# ESCs_2S.net
KiCad netlist of a schematic drawn in Altium Designer
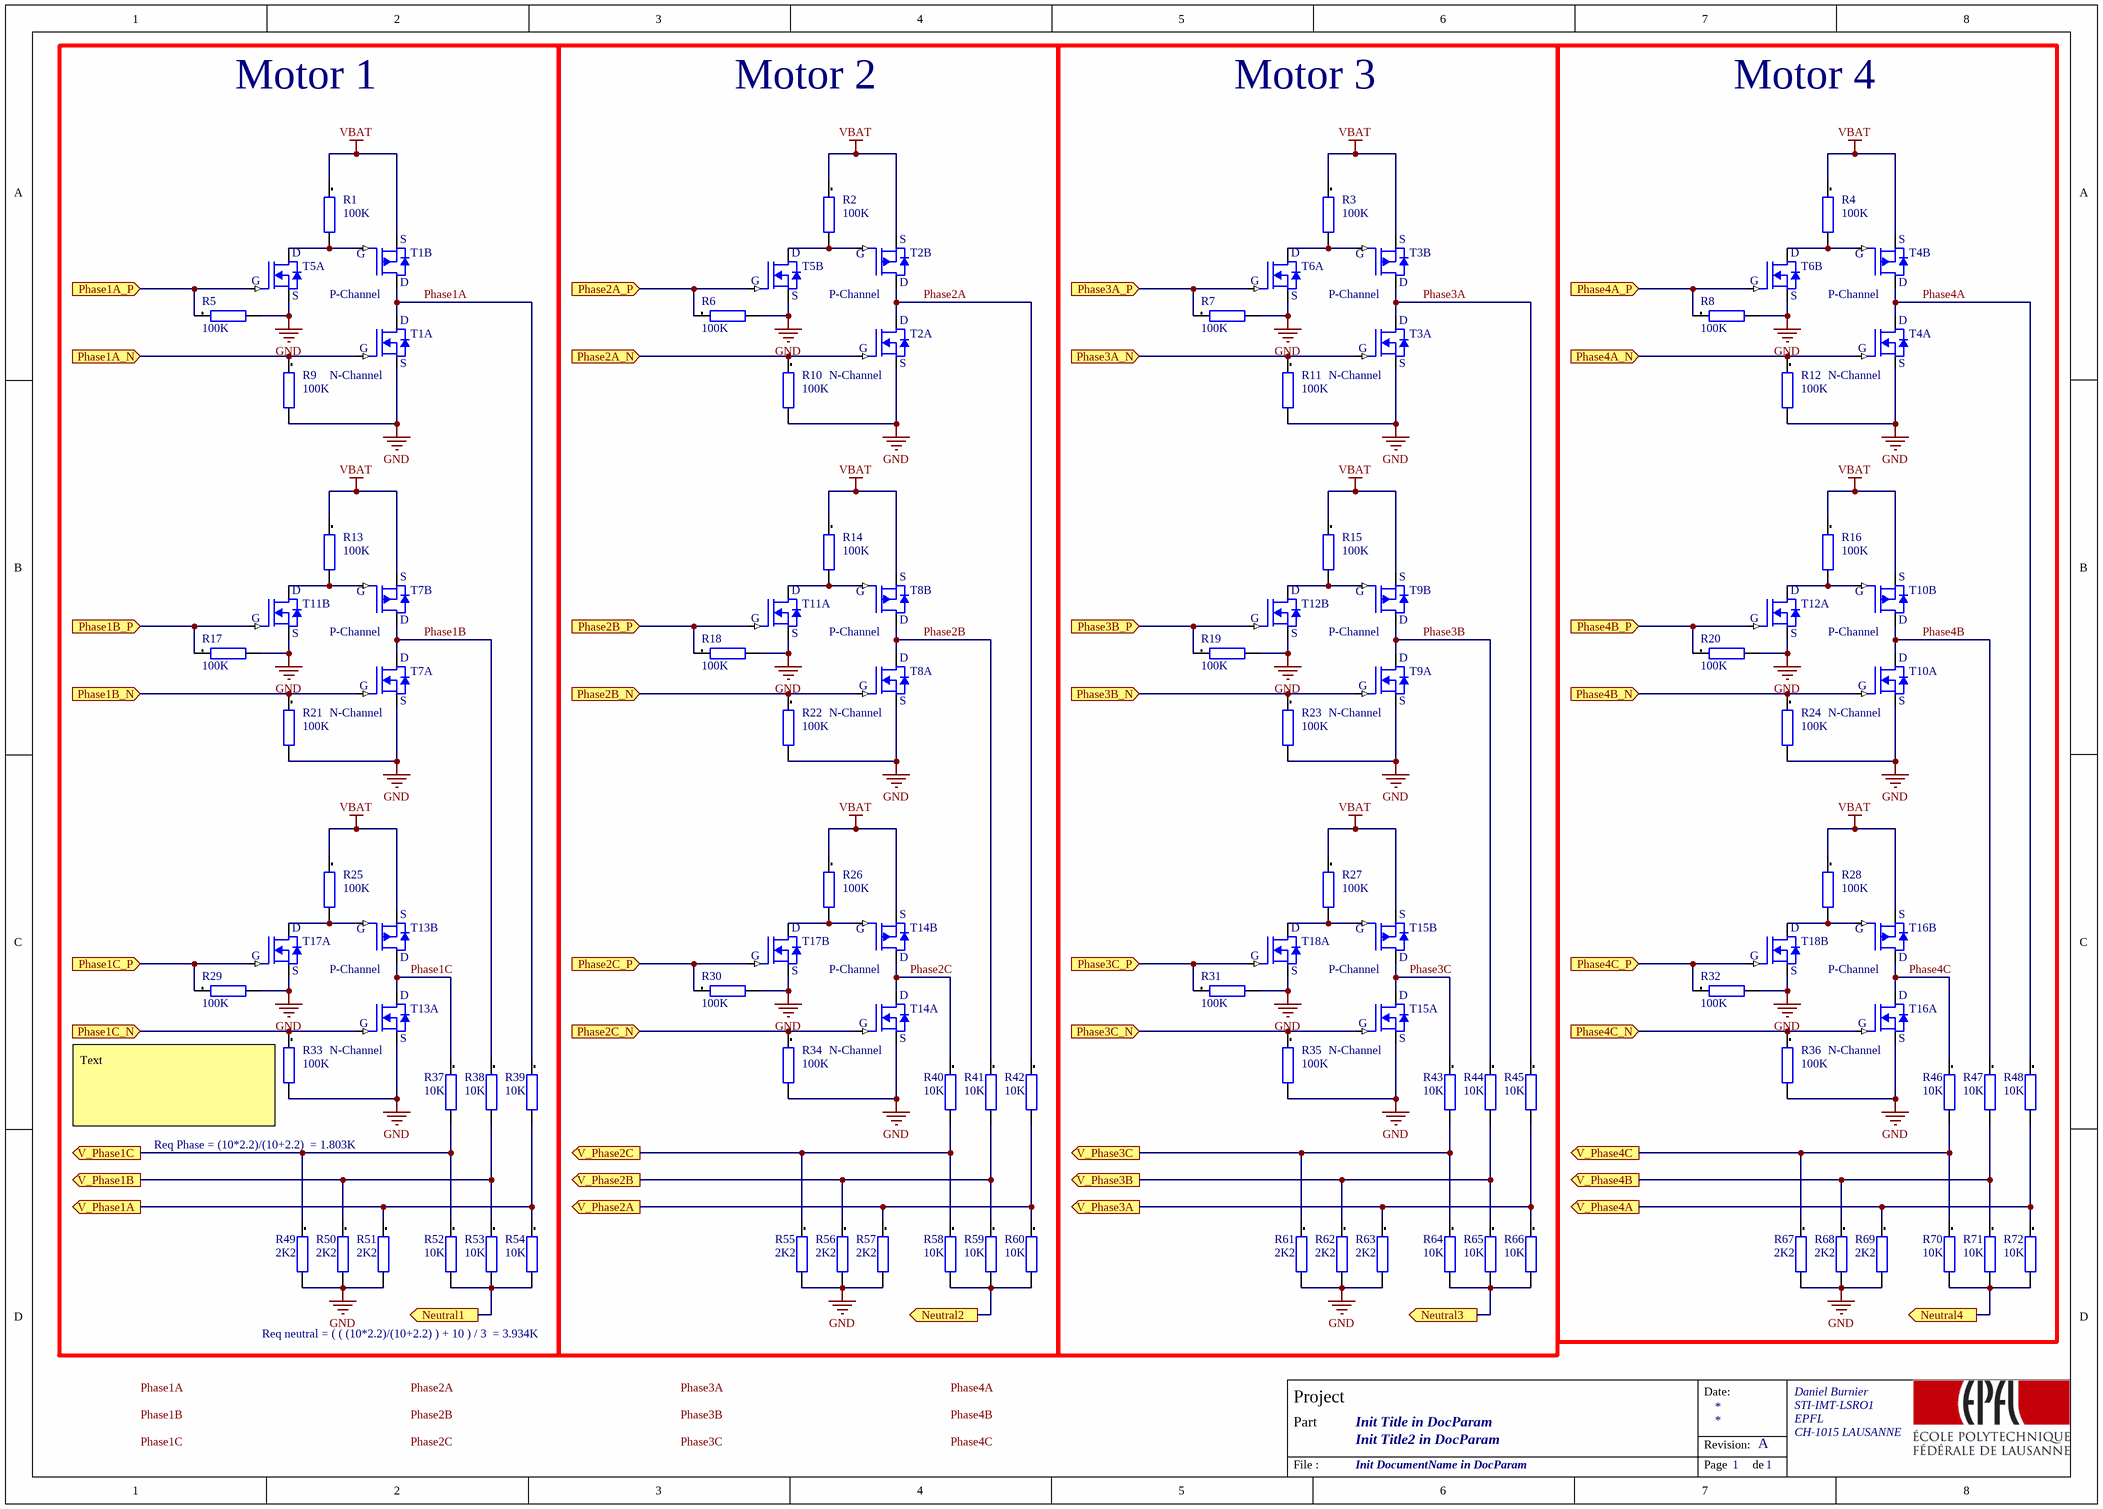
[diagram p0: ESCs_2S.SchDoc]

(export (version "E")
  (design (tool "Eeschema 10.0.6"))
  (components
    (comp (ref "R1")
      (value "100K")
      (footprint "RESC0201(0603)_L")
      (description "Resistor ToDo 0201")
      (libsource (lib "LSRO1Altium") (part "RES"))
    )
    (comp (ref "R2")
      (value "100K")
      (footprint "RESC0201(0603)_L")
      (description "Resistor ToDo 0201")
      (libsource (lib "LSRO1Altium") (part "RES"))
    )
    (comp (ref "R3")
      (value "100K")
      (footprint "RESC0201(0603)_L")
      (description "Resistor ToDo 0201")
      (libsource (lib "LSRO1Altium") (part "RES"))
    )
    (comp (ref "R4")
      (value "100K")
      (footprint "RESC0201(0603)_L")
      (description "Resistor ToDo 0201")
      (libsource (lib "LSRO1Altium") (part "RES"))
    )
    (comp (ref "R5")
      (value "100K")
      (footprint "RESC0201(0603)_L")
      (description "Resistor ToDo 0201")
      (libsource (lib "LSRO1Altium") (part "RES"))
    )
    (comp (ref "R6")
      (value "100K")
      (footprint "RESC0201(0603)_L")
      (description "Resistor ToDo 0201")
      (libsource (lib "LSRO1Altium") (part "RES"))
    )
    (comp (ref "R7")
      (value "100K")
      (footprint "RESC0201(0603)_L")
      (description "Resistor ToDo 0201")
      (libsource (lib "LSRO1Altium") (part "RES"))
    )
    (comp (ref "R8")
      (value "100K")
      (footprint "RESC0201(0603)_L")
      (description "Resistor ToDo 0201")
      (libsource (lib "LSRO1Altium") (part "RES"))
    )
    (comp (ref "R9")
      (value "100K")
      (footprint "RESC0201(0603)_L")
      (description "Resistor ToDo 0201")
      (libsource (lib "LSRO1Altium") (part "RES"))
    )
    (comp (ref "R10")
      (value "100K")
      (footprint "RESC0201(0603)_L")
      (description "Resistor ToDo 0201")
      (libsource (lib "LSRO1Altium") (part "RES"))
    )
    (comp (ref "R11")
      (value "100K")
      (footprint "RESC0201(0603)_L")
      (description "Resistor ToDo 0201")
      (libsource (lib "LSRO1Altium") (part "RES"))
    )
    (comp (ref "R12")
      (value "100K")
      (footprint "RESC0201(0603)_L")
      (description "Resistor ToDo 0201")
      (libsource (lib "LSRO1Altium") (part "RES"))
    )
    (comp (ref "R13")
      (value "100K")
      (footprint "RESC0201(0603)_L")
      (description "Resistor ToDo 0201")
      (libsource (lib "LSRO1Altium") (part "RES"))
    )
    (comp (ref "R14")
      (value "100K")
      (footprint "RESC0201(0603)_L")
      (description "Resistor ToDo 0201")
      (libsource (lib "LSRO1Altium") (part "RES"))
    )
    (comp (ref "R15")
      (value "100K")
      (footprint "RESC0201(0603)_L")
      (description "Resistor ToDo 0201")
      (libsource (lib "LSRO1Altium") (part "RES"))
    )
    (comp (ref "R16")
      (value "100K")
      (footprint "RESC0201(0603)_L")
      (description "Resistor ToDo 0201")
      (libsource (lib "LSRO1Altium") (part "RES"))
    )
    (comp (ref "R17")
      (value "100K")
      (footprint "RESC0201(0603)_L")
      (description "Resistor ToDo 0201")
      (libsource (lib "LSRO1Altium") (part "RES"))
    )
    (comp (ref "R18")
      (value "100K")
      (footprint "RESC0201(0603)_L")
      (description "Resistor ToDo 0201")
      (libsource (lib "LSRO1Altium") (part "RES"))
    )
    (comp (ref "R19")
      (value "100K")
      (footprint "RESC0201(0603)_L")
      (description "Resistor ToDo 0201")
      (libsource (lib "LSRO1Altium") (part "RES"))
    )
    (comp (ref "R20")
      (value "100K")
      (footprint "RESC0201(0603)_L")
      (description "Resistor ToDo 0201")
      (libsource (lib "LSRO1Altium") (part "RES"))
    )
    (comp (ref "R21")
      (value "100K")
      (footprint "RESC0201(0603)_L")
      (description "Resistor ToDo 0201")
      (libsource (lib "LSRO1Altium") (part "RES"))
    )
    (comp (ref "R22")
      (value "100K")
      (footprint "RESC0201(0603)_L")
      (description "Resistor ToDo 0201")
      (libsource (lib "LSRO1Altium") (part "RES"))
    )
    (comp (ref "R23")
      (value "100K")
      (footprint "RESC0201(0603)_L")
      (description "Resistor ToDo 0201")
      (libsource (lib "LSRO1Altium") (part "RES"))
    )
    (comp (ref "R24")
      (value "100K")
      (footprint "RESC0201(0603)_L")
      (description "Resistor ToDo 0201")
      (libsource (lib "LSRO1Altium") (part "RES"))
    )
    (comp (ref "R25")
      (value "100K")
      (footprint "RESC0201(0603)_L")
      (description "Resistor ToDo 0201")
      (libsource (lib "LSRO1Altium") (part "RES"))
    )
    (comp (ref "R26")
      (value "100K")
      (footprint "RESC0201(0603)_L")
      (description "Resistor ToDo 0201")
      (libsource (lib "LSRO1Altium") (part "RES"))
    )
    (comp (ref "R27")
      (value "100K")
      (footprint "RESC0201(0603)_L")
      (description "Resistor ToDo 0201")
      (libsource (lib "LSRO1Altium") (part "RES"))
    )
    (comp (ref "R28")
      (value "100K")
      (footprint "RESC0201(0603)_L")
      (description "Resistor ToDo 0201")
      (libsource (lib "LSRO1Altium") (part "RES"))
    )
    (comp (ref "R29")
      (value "100K")
      (footprint "RESC0201(0603)_L")
      (description "Resistor ToDo 0201")
      (libsource (lib "LSRO1Altium") (part "RES"))
    )
    (comp (ref "R30")
      (value "100K")
      (footprint "RESC0201(0603)_L")
      (description "Resistor ToDo 0201")
      (libsource (lib "LSRO1Altium") (part "RES"))
    )
    (comp (ref "R31")
      (value "100K")
      (footprint "RESC0201(0603)_L")
      (description "Resistor ToDo 0201")
      (libsource (lib "LSRO1Altium") (part "RES"))
    )
    (comp (ref "R32")
      (value "100K")
      (footprint "RESC0201(0603)_L")
      (description "Resistor ToDo 0201")
      (libsource (lib "LSRO1Altium") (part "RES"))
    )
    (comp (ref "R33")
      (value "100K")
      (footprint "RESC0201(0603)_L")
      (description "Resistor ToDo 0201")
      (libsource (lib "LSRO1Altium") (part "RES"))
    )
    (comp (ref "R34")
      (value "100K")
      (footprint "RESC0201(0603)_L")
      (description "Resistor ToDo 0201")
      (libsource (lib "LSRO1Altium") (part "RES"))
    )
    (comp (ref "R35")
      (value "100K")
      (footprint "RESC0201(0603)_L")
      (description "Resistor ToDo 0201")
      (libsource (lib "LSRO1Altium") (part "RES"))
    )
    (comp (ref "R36")
      (value "100K")
      (footprint "RESC0201(0603)_L")
      (description "Resistor ToDo 0201")
      (libsource (lib "LSRO1Altium") (part "RES"))
    )
    (comp (ref "R37")
      (value "10K")
      (footprint "RESC0201(0603)_L")
      (description "Resistor ToDo 0201")
      (libsource (lib "LSRO1Altium") (part "RES"))
    )
    (comp (ref "R38")
      (value "10K")
      (footprint "RESC0201(0603)_L")
      (description "Resistor ToDo 0201")
      (libsource (lib "LSRO1Altium") (part "RES"))
    )
    (comp (ref "R39")
      (value "10K")
      (footprint "RESC0201(0603)_L")
      (description "Resistor ToDo 0201")
      (libsource (lib "LSRO1Altium") (part "RES"))
    )
    (comp (ref "R40")
      (value "10K")
      (footprint "RESC0201(0603)_L")
      (description "Resistor ToDo 0201")
      (libsource (lib "LSRO1Altium") (part "RES"))
    )
    (comp (ref "R41")
      (value "10K")
      (footprint "RESC0201(0603)_L")
      (description "Resistor ToDo 0201")
      (libsource (lib "LSRO1Altium") (part "RES"))
    )
    (comp (ref "R42")
      (value "10K")
      (footprint "RESC0201(0603)_L")
      (description "Resistor ToDo 0201")
      (libsource (lib "LSRO1Altium") (part "RES"))
    )
    (comp (ref "R43")
      (value "10K")
      (footprint "RESC0201(0603)_L")
      (description "Resistor ToDo 0201")
      (libsource (lib "LSRO1Altium") (part "RES"))
    )
    (comp (ref "R44")
      (value "10K")
      (footprint "RESC0201(0603)_L")
      (description "Resistor ToDo 0201")
      (libsource (lib "LSRO1Altium") (part "RES"))
    )
    (comp (ref "R45")
      (value "10K")
      (footprint "RESC0201(0603)_L")
      (description "Resistor ToDo 0201")
      (libsource (lib "LSRO1Altium") (part "RES"))
    )
    (comp (ref "R46")
      (value "10K")
      (footprint "RESC0201(0603)_L")
      (description "Resistor ToDo 0201")
      (libsource (lib "LSRO1Altium") (part "RES"))
    )
    (comp (ref "R47")
      (value "10K")
      (footprint "RESC0201(0603)_L")
      (description "Resistor ToDo 0201")
      (libsource (lib "LSRO1Altium") (part "RES"))
    )
    (comp (ref "R48")
      (value "10K")
      (footprint "RESC0201(0603)_L")
      (description "Resistor ToDo 0201")
      (libsource (lib "LSRO1Altium") (part "RES"))
    )
    (comp (ref "R49")
      (value "2K2")
      (footprint "RESC0201(0603)_L")
      (description "Resistor ToDo 0201")
      (libsource (lib "LSRO1Altium") (part "RES"))
    )
    (comp (ref "R50")
      (value "2K2")
      (footprint "RESC0201(0603)_L")
      (description "Resistor ToDo 0201")
      (libsource (lib "LSRO1Altium") (part "RES"))
    )
    (comp (ref "R51")
      (value "2K2")
      (footprint "RESC0201(0603)_L")
      (description "Resistor ToDo 0201")
      (libsource (lib "LSRO1Altium") (part "RES"))
    )
    (comp (ref "R52")
      (value "10K")
      (footprint "RESC0201(0603)_L")
      (description "Resistor ToDo 0201")
      (libsource (lib "LSRO1Altium") (part "RES"))
    )
    (comp (ref "R53")
      (value "10K")
      (footprint "RESC0201(0603)_L")
      (description "Resistor ToDo 0201")
      (libsource (lib "LSRO1Altium") (part "RES"))
    )
    (comp (ref "R54")
      (value "10K")
      (footprint "RESC0201(0603)_L")
      (description "Resistor ToDo 0201")
      (libsource (lib "LSRO1Altium") (part "RES"))
    )
    (comp (ref "R55")
      (value "2K2")
      (footprint "RESC0201(0603)_L")
      (description "Resistor ToDo 0201")
      (libsource (lib "LSRO1Altium") (part "RES"))
    )
    (comp (ref "R56")
      (value "2K2")
      (footprint "RESC0201(0603)_L")
      (description "Resistor ToDo 0201")
      (libsource (lib "LSRO1Altium") (part "RES"))
    )
    (comp (ref "R57")
      (value "2K2")
      (footprint "RESC0201(0603)_L")
      (description "Resistor ToDo 0201")
      (libsource (lib "LSRO1Altium") (part "RES"))
    )
    (comp (ref "R58")
      (value "10K")
      (footprint "RESC0201(0603)_L")
      (description "Resistor ToDo 0201")
      (libsource (lib "LSRO1Altium") (part "RES"))
    )
    (comp (ref "R59")
      (value "10K")
      (footprint "RESC0201(0603)_L")
      (description "Resistor ToDo 0201")
      (libsource (lib "LSRO1Altium") (part "RES"))
    )
    (comp (ref "R60")
      (value "10K")
      (footprint "RESC0201(0603)_L")
      (description "Resistor ToDo 0201")
      (libsource (lib "LSRO1Altium") (part "RES"))
    )
    (comp (ref "R61")
      (value "2K2")
      (footprint "RESC0201(0603)_L")
      (description "Resistor ToDo 0201")
      (libsource (lib "LSRO1Altium") (part "RES"))
    )
    (comp (ref "R62")
      (value "2K2")
      (footprint "RESC0201(0603)_L")
      (description "Resistor ToDo 0201")
      (libsource (lib "LSRO1Altium") (part "RES"))
    )
    (comp (ref "R63")
      (value "2K2")
      (footprint "RESC0201(0603)_L")
      (description "Resistor ToDo 0201")
      (libsource (lib "LSRO1Altium") (part "RES"))
    )
    (comp (ref "R64")
      (value "10K")
      (footprint "RESC0201(0603)_L")
      (description "Resistor ToDo 0201")
      (libsource (lib "LSRO1Altium") (part "RES"))
    )
    (comp (ref "R65")
      (value "10K")
      (footprint "RESC0201(0603)_L")
      (description "Resistor ToDo 0201")
      (libsource (lib "LSRO1Altium") (part "RES"))
    )
    (comp (ref "R66")
      (value "10K")
      (footprint "RESC0201(0603)_L")
      (description "Resistor ToDo 0201")
      (libsource (lib "LSRO1Altium") (part "RES"))
    )
    (comp (ref "R67")
      (value "2K2")
      (footprint "RESC0201(0603)_L")
      (description "Resistor ToDo 0201")
      (libsource (lib "LSRO1Altium") (part "RES"))
    )
    (comp (ref "R68")
      (value "2K2")
      (footprint "RESC0201(0603)_L")
      (description "Resistor ToDo 0201")
      (libsource (lib "LSRO1Altium") (part "RES"))
    )
    (comp (ref "R69")
      (value "2K2")
      (footprint "RESC0201(0603)_L")
      (description "Resistor ToDo 0201")
      (libsource (lib "LSRO1Altium") (part "RES"))
    )
    (comp (ref "R70")
      (value "10K")
      (footprint "RESC0201(0603)_L")
      (description "Resistor ToDo 0201")
      (libsource (lib "LSRO1Altium") (part "RES"))
    )
    (comp (ref "R71")
      (value "10K")
      (footprint "RESC0201(0603)_L")
      (description "Resistor ToDo 0201")
      (libsource (lib "LSRO1Altium") (part "RES"))
    )
    (comp (ref "R72")
      (value "10K")
      (footprint "RESC0201(0603)_L")
      (description "Resistor ToDo 0201")
      (libsource (lib "LSRO1Altium") (part "RES"))
    )
    (comp (ref "T1")
      (value "ECH8668-TL-H")
      (footprint "8-SMD Flat lead")
      (description "MOSFET N/P-CH 20V 7.5A/5A ECH8")
      (fields (field (name "MANUFACTURER") "ON Semiconductor"))
      (libsource (lib "Schlib") (part "ECH8668-TL-H"))
    )
    (comp (ref "T2")
      (value "ECH8668-TL-H")
      (footprint "8-SMD Flat lead")
      (description "MOSFET N/P-CH 20V 7.5A/5A ECH8")
      (fields (field (name "MANUFACTURER") "ON Semiconductor"))
      (libsource (lib "Schlib") (part "ECH8668-TL-H"))
    )
    (comp (ref "T3")
      (value "ECH8668-TL-H")
      (footprint "8-SMD Flat lead")
      (description "MOSFET N/P-CH 20V 7.5A/5A ECH8")
      (fields (field (name "MANUFACTURER") "ON Semiconductor"))
      (libsource (lib "Schlib") (part "ECH8668-TL-H"))
    )
    (comp (ref "T4")
      (value "ECH8668-TL-H")
      (footprint "8-SMD Flat lead")
      (description "MOSFET N/P-CH 20V 7.5A/5A ECH8")
      (fields (field (name "MANUFACTURER") "ON Semiconductor"))
      (libsource (lib "Schlib") (part "ECH8668-TL-H"))
    )
    (comp (ref "T5")
      (value "PMDXB550UNEZ")
      (footprint "DFN1010B-6")
      (description "DUAL N-CHANNEL 30V")
      (fields (field (name "MANUFACTURER") "NXP Semiconductors"))
      (libsource (lib "Schlib") (part "PMDXB550UNEZ"))
    )
    (comp (ref "T6")
      (value "PMDXB550UNEZ")
      (footprint "DFN1010B-6")
      (description "DUAL N-CHANNEL 30V")
      (fields (field (name "MANUFACTURER") "NXP Semiconductors"))
      (libsource (lib "Schlib") (part "PMDXB550UNEZ"))
    )
    (comp (ref "T7")
      (value "ECH8668-TL-H")
      (footprint "8-SMD Flat lead")
      (description "MOSFET N/P-CH 20V 7.5A/5A ECH8")
      (fields (field (name "MANUFACTURER") "ON Semiconductor"))
      (libsource (lib "Schlib") (part "ECH8668-TL-H"))
    )
    (comp (ref "T8")
      (value "ECH8668-TL-H")
      (footprint "8-SMD Flat lead")
      (description "MOSFET N/P-CH 20V 7.5A/5A ECH8")
      (fields (field (name "MANUFACTURER") "ON Semiconductor"))
      (libsource (lib "Schlib") (part "ECH8668-TL-H"))
    )
    (comp (ref "T9")
      (value "ECH8668-TL-H")
      (footprint "8-SMD Flat lead")
      (description "MOSFET N/P-CH 20V 7.5A/5A ECH8")
      (fields (field (name "MANUFACTURER") "ON Semiconductor"))
      (libsource (lib "Schlib") (part "ECH8668-TL-H"))
    )
    (comp (ref "T10")
      (value "ECH8668-TL-H")
      (footprint "8-SMD Flat lead")
      (description "MOSFET N/P-CH 20V 7.5A/5A ECH8")
      (fields (field (name "MANUFACTURER") "ON Semiconductor"))
      (libsource (lib "Schlib") (part "ECH8668-TL-H"))
    )
    (comp (ref "T11")
      (value "PMDXB550UNEZ")
      (footprint "DFN1010B-6")
      (description "DUAL N-CHANNEL 30V")
      (fields (field (name "MANUFACTURER") "NXP Semiconductors"))
      (libsource (lib "Schlib") (part "PMDXB550UNEZ"))
    )
    (comp (ref "T12")
      (value "PMDXB550UNEZ")
      (footprint "DFN1010B-6")
      (description "DUAL N-CHANNEL 30V")
      (fields (field (name "MANUFACTURER") "NXP Semiconductors"))
      (libsource (lib "Schlib") (part "PMDXB550UNEZ"))
    )
    (comp (ref "T13")
      (value "ECH8668-TL-H")
      (footprint "8-SMD Flat lead")
      (description "MOSFET N/P-CH 20V 7.5A/5A ECH8")
      (fields (field (name "MANUFACTURER") "ON Semiconductor"))
      (libsource (lib "Schlib") (part "ECH8668-TL-H"))
    )
    (comp (ref "T14")
      (value "ECH8668-TL-H")
      (footprint "8-SMD Flat lead")
      (description "MOSFET N/P-CH 20V 7.5A/5A ECH8")
      (fields (field (name "MANUFACTURER") "ON Semiconductor"))
      (libsource (lib "Schlib") (part "ECH8668-TL-H"))
    )
    (comp (ref "T15")
      (value "ECH8668-TL-H")
      (footprint "8-SMD Flat lead")
      (description "MOSFET N/P-CH 20V 7.5A/5A ECH8")
      (fields (field (name "MANUFACTURER") "ON Semiconductor"))
      (libsource (lib "Schlib") (part "ECH8668-TL-H"))
    )
    (comp (ref "T16")
      (value "ECH8668-TL-H")
      (footprint "8-SMD Flat lead")
      (description "MOSFET N/P-CH 20V 7.5A/5A ECH8")
      (fields (field (name "MANUFACTURER") "ON Semiconductor"))
      (libsource (lib "Schlib") (part "ECH8668-TL-H"))
    )
    (comp (ref "T17")
      (value "PMDXB550UNEZ")
      (footprint "DFN1010B-6")
      (description "DUAL N-CHANNEL 30V")
      (fields (field (name "MANUFACTURER") "NXP Semiconductors"))
      (libsource (lib "Schlib") (part "PMDXB550UNEZ"))
    )
    (comp (ref "T18")
      (value "PMDXB550UNEZ")
      (footprint "DFN1010B-6")
      (description "DUAL N-CHANNEL 30V")
      (fields (field (name "MANUFACTURER") "NXP Semiconductors"))
      (libsource (lib "Schlib") (part "PMDXB550UNEZ"))
    )
  )
  (nets
    (net (code "1") (name "/Neutral1") (class "Default")
      (node (ref "R52") (pin "2") (pinfunction "2_2") (pintype "passive"))
      (node (ref "R53") (pin "2") (pinfunction "2_2") (pintype "passive"))
      (node (ref "R54") (pin "2") (pinfunction "2_2") (pintype "passive"))
    )
    (net (code "2") (name "/Neutral2") (class "Default")
      (node (ref "R58") (pin "2") (pinfunction "2_2") (pintype "passive"))
      (node (ref "R59") (pin "2") (pinfunction "2_2") (pintype "passive"))
      (node (ref "R60") (pin "2") (pinfunction "2_2") (pintype "passive"))
    )
    (net (code "3") (name "/Neutral3") (class "Default")
      (node (ref "R64") (pin "2") (pinfunction "2_2") (pintype "passive"))
      (node (ref "R65") (pin "2") (pinfunction "2_2") (pintype "passive"))
      (node (ref "R66") (pin "2") (pinfunction "2_2") (pintype "passive"))
    )
    (net (code "4") (name "/Neutral4") (class "Default")
      (node (ref "R70") (pin "2") (pinfunction "2_2") (pintype "passive"))
      (node (ref "R71") (pin "2") (pinfunction "2_2") (pintype "passive"))
      (node (ref "R72") (pin "2") (pinfunction "2_2") (pintype "passive"))
    )
    (net (code "5") (name "/Phase1A") (class "Default")
      (node (ref "R39") (pin "1") (pinfunction "1_1") (pintype "passive"))
      (node (ref "T1") (pin "5") (pinfunction "D_5") (pintype "passive"))
      (node (ref "T1") (pin "6") (pinfunction "D_6") (pintype "passive"))
    )
    (net (code "6") (name "/Phase1A_N") (class "Default")
      (node (ref "R9") (pin "1") (pinfunction "1_1") (pintype "passive"))
      (node (ref "T1") (pin "2") (pinfunction "G_2") (pintype "input"))
    )
    (net (code "7") (name "/Phase1A_P") (class "Default")
      (node (ref "R5") (pin "1") (pinfunction "1_1") (pintype "passive"))
      (node (ref "T5") (pin "2") (pinfunction "G_2") (pintype "input"))
    )
    (net (code "8") (name "/Phase1B") (class "Default")
      (node (ref "R38") (pin "1") (pinfunction "1_1") (pintype "passive"))
      (node (ref "T7") (pin "5") (pinfunction "D_5") (pintype "passive"))
      (node (ref "T7") (pin "6") (pinfunction "D_6") (pintype "passive"))
    )
    (net (code "9") (name "/Phase1B_N") (class "Default")
      (node (ref "R21") (pin "1") (pinfunction "1_1") (pintype "passive"))
      (node (ref "T7") (pin "2") (pinfunction "G_2") (pintype "input"))
    )
    (net (code "10") (name "/Phase1B_P") (class "Default")
      (node (ref "R17") (pin "1") (pinfunction "1_1") (pintype "passive"))
      (node (ref "T11") (pin "5") (pinfunction "G_5") (pintype "input"))
    )
    (net (code "11") (name "/Phase1C") (class "Default")
      (node (ref "R37") (pin "1") (pinfunction "1_1") (pintype "passive"))
      (node (ref "T13") (pin "5") (pinfunction "D_5") (pintype "passive"))
      (node (ref "T13") (pin "6") (pinfunction "D_6") (pintype "passive"))
    )
    (net (code "12") (name "/Phase1C_N") (class "Default")
      (node (ref "R33") (pin "1") (pinfunction "1_1") (pintype "passive"))
      (node (ref "T13") (pin "2") (pinfunction "G_2") (pintype "input"))
    )
    (net (code "13") (name "/Phase1C_P") (class "Default")
      (node (ref "R29") (pin "1") (pinfunction "1_1") (pintype "passive"))
      (node (ref "T17") (pin "2") (pinfunction "G_2") (pintype "input"))
    )
    (net (code "14") (name "/Phase2A") (class "Default")
      (node (ref "R42") (pin "1") (pinfunction "1_1") (pintype "passive"))
      (node (ref "T2") (pin "5") (pinfunction "D_5") (pintype "passive"))
      (node (ref "T2") (pin "6") (pinfunction "D_6") (pintype "passive"))
    )
    (net (code "15") (name "/Phase2A_N") (class "Default")
      (node (ref "R10") (pin "1") (pinfunction "1_1") (pintype "passive"))
      (node (ref "T2") (pin "2") (pinfunction "G_2") (pintype "input"))
    )
    (net (code "16") (name "/Phase2A_P") (class "Default")
      (node (ref "R6") (pin "1") (pinfunction "1_1") (pintype "passive"))
      (node (ref "T5") (pin "5") (pinfunction "G_5") (pintype "input"))
    )
    (net (code "17") (name "/Phase2B") (class "Default")
      (node (ref "R41") (pin "1") (pinfunction "1_1") (pintype "passive"))
      (node (ref "T8") (pin "5") (pinfunction "D_5") (pintype "passive"))
      (node (ref "T8") (pin "6") (pinfunction "D_6") (pintype "passive"))
    )
    (net (code "18") (name "/Phase2B_N") (class "Default")
      (node (ref "R22") (pin "1") (pinfunction "1_1") (pintype "passive"))
      (node (ref "T8") (pin "2") (pinfunction "G_2") (pintype "input"))
    )
    (net (code "19") (name "/Phase2B_P") (class "Default")
      (node (ref "R18") (pin "1") (pinfunction "1_1") (pintype "passive"))
      (node (ref "T11") (pin "2") (pinfunction "G_2") (pintype "input"))
    )
    (net (code "20") (name "/Phase2C") (class "Default")
      (node (ref "R40") (pin "1") (pinfunction "1_1") (pintype "passive"))
      (node (ref "T14") (pin "5") (pinfunction "D_5") (pintype "passive"))
      (node (ref "T14") (pin "6") (pinfunction "D_6") (pintype "passive"))
    )
    (net (code "21") (name "/Phase2C_N") (class "Default")
      (node (ref "R34") (pin "1") (pinfunction "1_1") (pintype "passive"))
      (node (ref "T14") (pin "2") (pinfunction "G_2") (pintype "input"))
    )
    (net (code "22") (name "/Phase2C_P") (class "Default")
      (node (ref "R30") (pin "1") (pinfunction "1_1") (pintype "passive"))
      (node (ref "T17") (pin "5") (pinfunction "G_5") (pintype "input"))
    )
    (net (code "23") (name "/Phase3A") (class "Default")
      (node (ref "R45") (pin "1") (pinfunction "1_1") (pintype "passive"))
      (node (ref "T3") (pin "5") (pinfunction "D_5") (pintype "passive"))
      (node (ref "T3") (pin "6") (pinfunction "D_6") (pintype "passive"))
    )
    (net (code "24") (name "/Phase3A_N") (class "Default")
      (node (ref "R11") (pin "1") (pinfunction "1_1") (pintype "passive"))
      (node (ref "T3") (pin "2") (pinfunction "G_2") (pintype "input"))
    )
    (net (code "25") (name "/Phase3A_P") (class "Default")
      (node (ref "R7") (pin "1") (pinfunction "1_1") (pintype "passive"))
      (node (ref "T6") (pin "2") (pinfunction "G_2") (pintype "input"))
    )
    (net (code "26") (name "/Phase3B") (class "Default")
      (node (ref "R44") (pin "1") (pinfunction "1_1") (pintype "passive"))
      (node (ref "T9") (pin "5") (pinfunction "D_5") (pintype "passive"))
      (node (ref "T9") (pin "6") (pinfunction "D_6") (pintype "passive"))
    )
    (net (code "27") (name "/Phase3B_N") (class "Default")
      (node (ref "R23") (pin "1") (pinfunction "1_1") (pintype "passive"))
      (node (ref "T9") (pin "2") (pinfunction "G_2") (pintype "input"))
    )
    (net (code "28") (name "/Phase3B_P") (class "Default")
      (node (ref "R19") (pin "1") (pinfunction "1_1") (pintype "passive"))
      (node (ref "T12") (pin "5") (pinfunction "G_5") (pintype "input"))
    )
    (net (code "29") (name "/Phase3C") (class "Default")
      (node (ref "R43") (pin "1") (pinfunction "1_1") (pintype "passive"))
      (node (ref "T15") (pin "5") (pinfunction "D_5") (pintype "passive"))
      (node (ref "T15") (pin "6") (pinfunction "D_6") (pintype "passive"))
    )
    (net (code "30") (name "/Phase3C_N") (class "Default")
      (node (ref "R35") (pin "1") (pinfunction "1_1") (pintype "passive"))
      (node (ref "T15") (pin "2") (pinfunction "G_2") (pintype "input"))
    )
    (net (code "31") (name "/Phase3C_P") (class "Default")
      (node (ref "R31") (pin "1") (pinfunction "1_1") (pintype "passive"))
      (node (ref "T18") (pin "2") (pinfunction "G_2") (pintype "input"))
    )
    (net (code "32") (name "/Phase4A") (class "Default")
      (node (ref "R48") (pin "1") (pinfunction "1_1") (pintype "passive"))
      (node (ref "T4") (pin "5") (pinfunction "D_5") (pintype "passive"))
      (node (ref "T4") (pin "6") (pinfunction "D_6") (pintype "passive"))
    )
    (net (code "33") (name "/Phase4A_N") (class "Default")
      (node (ref "R12") (pin "1") (pinfunction "1_1") (pintype "passive"))
      (node (ref "T4") (pin "2") (pinfunction "G_2") (pintype "input"))
    )
    (net (code "34") (name "/Phase4A_P") (class "Default")
      (node (ref "R8") (pin "1") (pinfunction "1_1") (pintype "passive"))
      (node (ref "T6") (pin "5") (pinfunction "G_5") (pintype "input"))
    )
    (net (code "35") (name "/Phase4B") (class "Default")
      (node (ref "R47") (pin "1") (pinfunction "1_1") (pintype "passive"))
      (node (ref "T10") (pin "5") (pinfunction "D_5") (pintype "passive"))
      (node (ref "T10") (pin "6") (pinfunction "D_6") (pintype "passive"))
    )
    (net (code "36") (name "/Phase4B_N") (class "Default")
      (node (ref "R24") (pin "1") (pinfunction "1_1") (pintype "passive"))
      (node (ref "T10") (pin "2") (pinfunction "G_2") (pintype "input"))
    )
    (net (code "37") (name "/Phase4B_P") (class "Default")
      (node (ref "R20") (pin "1") (pinfunction "1_1") (pintype "passive"))
      (node (ref "T12") (pin "2") (pinfunction "G_2") (pintype "input"))
    )
    (net (code "38") (name "/Phase4C") (class "Default")
      (node (ref "R46") (pin "1") (pinfunction "1_1") (pintype "passive"))
      (node (ref "T16") (pin "5") (pinfunction "D_5") (pintype "passive"))
      (node (ref "T16") (pin "6") (pinfunction "D_6") (pintype "passive"))
    )
    (net (code "39") (name "/Phase4C_N") (class "Default")
      (node (ref "R36") (pin "1") (pinfunction "1_1") (pintype "passive"))
      (node (ref "T16") (pin "2") (pinfunction "G_2") (pintype "input"))
    )
    (net (code "40") (name "/Phase4C_P") (class "Default")
      (node (ref "R32") (pin "1") (pinfunction "1_1") (pintype "passive"))
      (node (ref "T18") (pin "5") (pinfunction "G_5") (pintype "input"))
    )
    (net (code "41") (name "/V_Phase1A") (class "Default")
      (node (ref "R39") (pin "2") (pinfunction "2_2") (pintype "passive"))
      (node (ref "R51") (pin "1") (pinfunction "1_1") (pintype "passive"))
      (node (ref "R54") (pin "1") (pinfunction "1_1") (pintype "passive"))
    )
    (net (code "42") (name "/V_Phase1B") (class "Default")
      (node (ref "R38") (pin "2") (pinfunction "2_2") (pintype "passive"))
      (node (ref "R50") (pin "1") (pinfunction "1_1") (pintype "passive"))
      (node (ref "R53") (pin "1") (pinfunction "1_1") (pintype "passive"))
    )
    (net (code "43") (name "/V_Phase1C") (class "Default")
      (node (ref "R37") (pin "2") (pinfunction "2_2") (pintype "passive"))
      (node (ref "R49") (pin "1") (pinfunction "1_1") (pintype "passive"))
      (node (ref "R52") (pin "1") (pinfunction "1_1") (pintype "passive"))
    )
    (net (code "44") (name "/V_Phase2A") (class "Default")
      (node (ref "R42") (pin "2") (pinfunction "2_2") (pintype "passive"))
      (node (ref "R57") (pin "1") (pinfunction "1_1") (pintype "passive"))
      (node (ref "R60") (pin "1") (pinfunction "1_1") (pintype "passive"))
    )
    (net (code "45") (name "/V_Phase2B") (class "Default")
      (node (ref "R41") (pin "2") (pinfunction "2_2") (pintype "passive"))
      (node (ref "R56") (pin "1") (pinfunction "1_1") (pintype "passive"))
      (node (ref "R59") (pin "1") (pinfunction "1_1") (pintype "passive"))
    )
    (net (code "46") (name "/V_Phase2C") (class "Default")
      (node (ref "R40") (pin "2") (pinfunction "2_2") (pintype "passive"))
      (node (ref "R55") (pin "1") (pinfunction "1_1") (pintype "passive"))
      (node (ref "R58") (pin "1") (pinfunction "1_1") (pintype "passive"))
    )
    (net (code "47") (name "/V_Phase3A") (class "Default")
      (node (ref "R45") (pin "2") (pinfunction "2_2") (pintype "passive"))
      (node (ref "R63") (pin "1") (pinfunction "1_1") (pintype "passive"))
      (node (ref "R66") (pin "1") (pinfunction "1_1") (pintype "passive"))
    )
    (net (code "48") (name "/V_Phase3B") (class "Default")
      (node (ref "R44") (pin "2") (pinfunction "2_2") (pintype "passive"))
      (node (ref "R62") (pin "1") (pinfunction "1_1") (pintype "passive"))
      (node (ref "R65") (pin "1") (pinfunction "1_1") (pintype "passive"))
    )
    (net (code "49") (name "/V_Phase3C") (class "Default")
      (node (ref "R43") (pin "2") (pinfunction "2_2") (pintype "passive"))
      (node (ref "R61") (pin "1") (pinfunction "1_1") (pintype "passive"))
      (node (ref "R64") (pin "1") (pinfunction "1_1") (pintype "passive"))
    )
    (net (code "50") (name "/V_Phase4A") (class "Default")
      (node (ref "R48") (pin "2") (pinfunction "2_2") (pintype "passive"))
      (node (ref "R69") (pin "1") (pinfunction "1_1") (pintype "passive"))
      (node (ref "R72") (pin "1") (pinfunction "1_1") (pintype "passive"))
    )
    (net (code "51") (name "/V_Phase4B") (class "Default")
      (node (ref "R47") (pin "2") (pinfunction "2_2") (pintype "passive"))
      (node (ref "R68") (pin "1") (pinfunction "1_1") (pintype "passive"))
      (node (ref "R71") (pin "1") (pinfunction "1_1") (pintype "passive"))
    )
    (net (code "52") (name "/V_Phase4C") (class "Default")
      (node (ref "R46") (pin "2") (pinfunction "2_2") (pintype "passive"))
      (node (ref "R67") (pin "1") (pinfunction "1_1") (pintype "passive"))
      (node (ref "R70") (pin "1") (pinfunction "1_1") (pintype "passive"))
    )
    (net (code "53") (name "GND") (class "Default")
      (node (ref "R10") (pin "2") (pinfunction "2_2") (pintype "passive"))
      (node (ref "R11") (pin "2") (pinfunction "2_2") (pintype "passive"))
      (node (ref "R12") (pin "2") (pinfunction "2_2") (pintype "passive"))
      (node (ref "R17") (pin "2") (pinfunction "2_2") (pintype "passive"))
      (node (ref "R18") (pin "2") (pinfunction "2_2") (pintype "passive"))
      (node (ref "R19") (pin "2") (pinfunction "2_2") (pintype "passive"))
      (node (ref "R20") (pin "2") (pinfunction "2_2") (pintype "passive"))
      (node (ref "R21") (pin "2") (pinfunction "2_2") (pintype "passive"))
      (node (ref "R22") (pin "2") (pinfunction "2_2") (pintype "passive"))
      (node (ref "R23") (pin "2") (pinfunction "2_2") (pintype "passive"))
      (node (ref "R24") (pin "2") (pinfunction "2_2") (pintype "passive"))
      (node (ref "R29") (pin "2") (pinfunction "2_2") (pintype "passive"))
      (node (ref "R30") (pin "2") (pinfunction "2_2") (pintype "passive"))
      (node (ref "R31") (pin "2") (pinfunction "2_2") (pintype "passive"))
      (node (ref "R32") (pin "2") (pinfunction "2_2") (pintype "passive"))
      (node (ref "R33") (pin "2") (pinfunction "2_2") (pintype "passive"))
      (node (ref "R34") (pin "2") (pinfunction "2_2") (pintype "passive"))
      (node (ref "R35") (pin "2") (pinfunction "2_2") (pintype "passive"))
      (node (ref "R36") (pin "2") (pinfunction "2_2") (pintype "passive"))
      (node (ref "R49") (pin "2") (pinfunction "2_2") (pintype "passive"))
      (node (ref "R5") (pin "2") (pinfunction "2_2") (pintype "passive"))
      (node (ref "R50") (pin "2") (pinfunction "2_2") (pintype "passive"))
      (node (ref "R51") (pin "2") (pinfunction "2_2") (pintype "passive"))
      (node (ref "R55") (pin "2") (pinfunction "2_2") (pintype "passive"))
      (node (ref "R56") (pin "2") (pinfunction "2_2") (pintype "passive"))
      (node (ref "R57") (pin "2") (pinfunction "2_2") (pintype "passive"))
      (node (ref "R6") (pin "2") (pinfunction "2_2") (pintype "passive"))
      (node (ref "R61") (pin "2") (pinfunction "2_2") (pintype "passive"))
      (node (ref "R62") (pin "2") (pinfunction "2_2") (pintype "passive"))
      (node (ref "R63") (pin "2") (pinfunction "2_2") (pintype "passive"))
      (node (ref "R67") (pin "2") (pinfunction "2_2") (pintype "passive"))
      (node (ref "R68") (pin "2") (pinfunction "2_2") (pintype "passive"))
      (node (ref "R69") (pin "2") (pinfunction "2_2") (pintype "passive"))
      (node (ref "R7") (pin "2") (pinfunction "2_2") (pintype "passive"))
      (node (ref "R8") (pin "2") (pinfunction "2_2") (pintype "passive"))
      (node (ref "R9") (pin "2") (pinfunction "2_2") (pintype "passive"))
      (node (ref "T1") (pin "1") (pinfunction "S_1") (pintype "passive"))
      (node (ref "T10") (pin "1") (pinfunction "S_1") (pintype "passive"))
      (node (ref "T11") (pin "1") (pinfunction "S_1") (pintype "passive"))
      (node (ref "T11") (pin "4") (pinfunction "S_4") (pintype "passive"))
      (node (ref "T12") (pin "1") (pinfunction "S_1") (pintype "passive"))
      (node (ref "T12") (pin "4") (pinfunction "S_4") (pintype "passive"))
      (node (ref "T13") (pin "1") (pinfunction "S_1") (pintype "passive"))
      (node (ref "T14") (pin "1") (pinfunction "S_1") (pintype "passive"))
      (node (ref "T15") (pin "1") (pinfunction "S_1") (pintype "passive"))
      (node (ref "T16") (pin "1") (pinfunction "S_1") (pintype "passive"))
      (node (ref "T17") (pin "1") (pinfunction "S_1") (pintype "passive"))
      (node (ref "T17") (pin "4") (pinfunction "S_4") (pintype "passive"))
      (node (ref "T18") (pin "1") (pinfunction "S_1") (pintype "passive"))
      (node (ref "T18") (pin "4") (pinfunction "S_4") (pintype "passive"))
      (node (ref "T2") (pin "1") (pinfunction "S_1") (pintype "passive"))
      (node (ref "T3") (pin "1") (pinfunction "S_1") (pintype "passive"))
      (node (ref "T4") (pin "1") (pinfunction "S_1") (pintype "passive"))
      (node (ref "T5") (pin "1") (pinfunction "S_1") (pintype "passive"))
      (node (ref "T5") (pin "4") (pinfunction "S_4") (pintype "passive"))
      (node (ref "T6") (pin "1") (pinfunction "S_1") (pintype "passive"))
      (node (ref "T6") (pin "4") (pinfunction "S_4") (pintype "passive"))
      (node (ref "T7") (pin "1") (pinfunction "S_1") (pintype "passive"))
      (node (ref "T8") (pin "1") (pinfunction "S_1") (pintype "passive"))
      (node (ref "T9") (pin "1") (pinfunction "S_1") (pintype "passive"))
    )
    (net (code "54") (name "Net-(T1B-G)") (class "Default")
      (node (ref "R1") (pin "2") (pinfunction "2_2") (pintype "passive"))
      (node (ref "T1") (pin "4") (pinfunction "G_4") (pintype "input"))
      (node (ref "T5") (pin "6") (pinfunction "D_6") (pintype "passive"))
    )
    (net (code "55") (name "Net-(T2B-G)") (class "Default")
      (node (ref "R2") (pin "2") (pinfunction "2_2") (pintype "passive"))
      (node (ref "T2") (pin "4") (pinfunction "G_4") (pintype "input"))
      (node (ref "T5") (pin "3") (pinfunction "D_3") (pintype "passive"))
    )
    (net (code "56") (name "Net-(T3B-G)") (class "Default")
      (node (ref "R3") (pin "2") (pinfunction "2_2") (pintype "passive"))
      (node (ref "T3") (pin "4") (pinfunction "G_4") (pintype "input"))
      (node (ref "T6") (pin "6") (pinfunction "D_6") (pintype "passive"))
    )
    (net (code "57") (name "Net-(T4B-G)") (class "Default")
      (node (ref "R4") (pin "2") (pinfunction "2_2") (pintype "passive"))
      (node (ref "T4") (pin "4") (pinfunction "G_4") (pintype "input"))
      (node (ref "T6") (pin "3") (pinfunction "D_3") (pintype "passive"))
    )
    (net (code "58") (name "Net-(T10B-G)") (class "Default")
      (node (ref "R16") (pin "2") (pinfunction "2_2") (pintype "passive"))
      (node (ref "T10") (pin "4") (pinfunction "G_4") (pintype "input"))
      (node (ref "T12") (pin "6") (pinfunction "D_6") (pintype "passive"))
    )
    (net (code "59") (name "Net-(T11A-D)") (class "Default")
      (node (ref "R14") (pin "2") (pinfunction "2_2") (pintype "passive"))
      (node (ref "T11") (pin "6") (pinfunction "D_6") (pintype "passive"))
      (node (ref "T8") (pin "4") (pinfunction "G_4") (pintype "input"))
    )
    (net (code "60") (name "Net-(T11B-D)") (class "Default")
      (node (ref "R13") (pin "2") (pinfunction "2_2") (pintype "passive"))
      (node (ref "T11") (pin "3") (pinfunction "D_3") (pintype "passive"))
      (node (ref "T7") (pin "4") (pinfunction "G_4") (pintype "input"))
    )
    (net (code "61") (name "Net-(T12B-D)") (class "Default")
      (node (ref "R15") (pin "2") (pinfunction "2_2") (pintype "passive"))
      (node (ref "T12") (pin "3") (pinfunction "D_3") (pintype "passive"))
      (node (ref "T9") (pin "4") (pinfunction "G_4") (pintype "input"))
    )
    (net (code "62") (name "Net-(T13B-G)") (class "Default")
      (node (ref "R25") (pin "2") (pinfunction "2_2") (pintype "passive"))
      (node (ref "T13") (pin "4") (pinfunction "G_4") (pintype "input"))
      (node (ref "T17") (pin "6") (pinfunction "D_6") (pintype "passive"))
    )
    (net (code "63") (name "Net-(T14B-G)") (class "Default")
      (node (ref "R26") (pin "2") (pinfunction "2_2") (pintype "passive"))
      (node (ref "T14") (pin "4") (pinfunction "G_4") (pintype "input"))
      (node (ref "T17") (pin "3") (pinfunction "D_3") (pintype "passive"))
    )
    (net (code "64") (name "Net-(T15B-G)") (class "Default")
      (node (ref "R27") (pin "2") (pinfunction "2_2") (pintype "passive"))
      (node (ref "T15") (pin "4") (pinfunction "G_4") (pintype "input"))
      (node (ref "T18") (pin "6") (pinfunction "D_6") (pintype "passive"))
    )
    (net (code "65") (name "Net-(T16B-G)") (class "Default")
      (node (ref "R28") (pin "2") (pinfunction "2_2") (pintype "passive"))
      (node (ref "T16") (pin "4") (pinfunction "G_4") (pintype "input"))
      (node (ref "T18") (pin "3") (pinfunction "D_3") (pintype "passive"))
    )
    (net (code "66") (name "VBAT") (class "Default")
      (node (ref "R1") (pin "1") (pinfunction "1_1") (pintype "passive"))
      (node (ref "R13") (pin "1") (pinfunction "1_1") (pintype "passive"))
      (node (ref "R14") (pin "1") (pinfunction "1_1") (pintype "passive"))
      (node (ref "R15") (pin "1") (pinfunction "1_1") (pintype "passive"))
      (node (ref "R16") (pin "1") (pinfunction "1_1") (pintype "passive"))
      (node (ref "R2") (pin "1") (pinfunction "1_1") (pintype "passive"))
      (node (ref "R25") (pin "1") (pinfunction "1_1") (pintype "passive"))
      (node (ref "R26") (pin "1") (pinfunction "1_1") (pintype "passive"))
      (node (ref "R27") (pin "1") (pinfunction "1_1") (pintype "passive"))
      (node (ref "R28") (pin "1") (pinfunction "1_1") (pintype "passive"))
      (node (ref "R3") (pin "1") (pinfunction "1_1") (pintype "passive"))
      (node (ref "R4") (pin "1") (pinfunction "1_1") (pintype "passive"))
      (node (ref "T1") (pin "3") (pinfunction "S_3") (pintype "passive"))
      (node (ref "T10") (pin "3") (pinfunction "S_3") (pintype "passive"))
      (node (ref "T13") (pin "3") (pinfunction "S_3") (pintype "passive"))
      (node (ref "T14") (pin "3") (pinfunction "S_3") (pintype "passive"))
      (node (ref "T15") (pin "3") (pinfunction "S_3") (pintype "passive"))
      (node (ref "T16") (pin "3") (pinfunction "S_3") (pintype "passive"))
      (node (ref "T2") (pin "3") (pinfunction "S_3") (pintype "passive"))
      (node (ref "T3") (pin "3") (pinfunction "S_3") (pintype "passive"))
      (node (ref "T4") (pin "3") (pinfunction "S_3") (pintype "passive"))
      (node (ref "T7") (pin "3") (pinfunction "S_3") (pintype "passive"))
      (node (ref "T8") (pin "3") (pinfunction "S_3") (pintype "passive"))
      (node (ref "T9") (pin "3") (pinfunction "S_3") (pintype "passive"))
    )
  )
)
